# contrl.net
KiCad netlist of a schematic drawn in Altium Designer
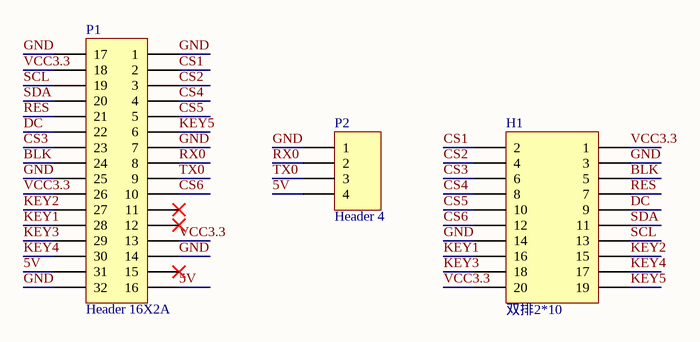
[diagram p0: contrl.SchDoc]

(export (version "E")
  (design (tool "Eeschema 10.0.6"))
  (components
    (comp (ref "H1") (value "双排2*10") (footprint "20pin") (libsource (lib "displayLCD") (part "双排2*10")))
    (comp (ref "P1")
      (value "Header 16X2A")
      (footprint "合宙esp32-c3开发板底座")
      (description "Header, 16-Pin, Dual row")
      (fields (field (name "PUBLISHER") "Altium Limited"))
      (libsource (lib "Miscellaneous Connectors") (part "Header 16X2A"))
    )
    (comp (ref "P2")
      (value "Header 4")
      (footprint "HDR1X4")
      (description "Header, 4-Pin")
      (fields (field (name "PUBLISHER") "Altium Limited"))
      (libsource (lib "Miscellaneous Connectors") (part "Header 4"))
    )
  )
  (nets
    (net (code "1") (name "/5V") (class "Default")
      (node (ref "P1") (pin "16") (pinfunction "16_16") (pintype "passive"))
      (node (ref "P1") (pin "31") (pinfunction "31_31") (pintype "passive"))
      (node (ref "P2") (pin "4") (pinfunction "4_4") (pintype "passive"))
    )
    (net (code "2") (name "/BLK") (class "Default")
      (node (ref "H1") (pin "5") (pinfunction "5_5") (pintype "passive"))
      (node (ref "P1") (pin "24") (pinfunction "24_24") (pintype "passive"))
    )
    (net (code "3") (name "/CS1") (class "Default")
      (node (ref "H1") (pin "2") (pinfunction "2_2") (pintype "passive"))
      (node (ref "P1") (pin "2") (pinfunction "2_2") (pintype "passive"))
    )
    (net (code "4") (name "/CS2") (class "Default")
      (node (ref "H1") (pin "4") (pinfunction "4_4") (pintype "passive"))
      (node (ref "P1") (pin "3") (pinfunction "3_3") (pintype "passive"))
    )
    (net (code "5") (name "/CS3") (class "Default")
      (node (ref "H1") (pin "6") (pinfunction "6_6") (pintype "passive"))
      (node (ref "P1") (pin "23") (pinfunction "23_23") (pintype "passive"))
    )
    (net (code "6") (name "/CS4") (class "Default")
      (node (ref "H1") (pin "8") (pinfunction "8_8") (pintype "passive"))
      (node (ref "P1") (pin "4") (pinfunction "4_4") (pintype "passive"))
    )
    (net (code "7") (name "/CS5") (class "Default")
      (node (ref "H1") (pin "10") (pinfunction "10_10") (pintype "passive"))
      (node (ref "P1") (pin "5") (pinfunction "5_5") (pintype "passive"))
    )
    (net (code "8") (name "/CS6") (class "Default")
      (node (ref "H1") (pin "12") (pinfunction "12_12") (pintype "passive"))
      (node (ref "P1") (pin "10") (pinfunction "10_10") (pintype "passive"))
    )
    (net (code "9") (name "/DC") (class "Default")
      (node (ref "H1") (pin "9") (pinfunction "9_9") (pintype "passive"))
      (node (ref "P1") (pin "22") (pinfunction "22_22") (pintype "passive"))
    )
    (net (code "10") (name "/GND") (class "Default")
      (node (ref "H1") (pin "14") (pinfunction "14_14") (pintype "passive"))
      (node (ref "H1") (pin "3") (pinfunction "3_3") (pintype "passive"))
      (node (ref "P1") (pin "1") (pinfunction "1_1") (pintype "passive"))
      (node (ref "P1") (pin "14") (pinfunction "14_14") (pintype "passive"))
      (node (ref "P1") (pin "17") (pinfunction "17_17") (pintype "passive"))
      (node (ref "P1") (pin "25") (pinfunction "25_25") (pintype "passive"))
      (node (ref "P1") (pin "32") (pinfunction "32_32") (pintype "passive"))
      (node (ref "P1") (pin "7") (pinfunction "7_7") (pintype "passive"))
      (node (ref "P2") (pin "1") (pinfunction "1_1") (pintype "passive"))
    )
    (net (code "11") (name "/KEY1") (class "Default")
      (node (ref "H1") (pin "16") (pinfunction "16_16") (pintype "passive"))
      (node (ref "P1") (pin "28") (pinfunction "28_28") (pintype "passive"))
    )
    (net (code "12") (name "/KEY2") (class "Default")
      (node (ref "H1") (pin "15") (pinfunction "15_15") (pintype "passive"))
      (node (ref "P1") (pin "27") (pinfunction "27_27") (pintype "passive"))
    )
    (net (code "13") (name "/KEY3") (class "Default")
      (node (ref "H1") (pin "18") (pinfunction "18_18") (pintype "passive"))
      (node (ref "P1") (pin "29") (pinfunction "29_29") (pintype "passive"))
    )
    (net (code "14") (name "/KEY4") (class "Default")
      (node (ref "H1") (pin "17") (pinfunction "17_17") (pintype "passive"))
      (node (ref "P1") (pin "30") (pinfunction "30_30") (pintype "passive"))
    )
    (net (code "15") (name "/KEY5") (class "Default")
      (node (ref "H1") (pin "19") (pinfunction "19_19") (pintype "passive"))
      (node (ref "P1") (pin "6") (pinfunction "6_6") (pintype "passive"))
    )
    (net (code "16") (name "/RES") (class "Default")
      (node (ref "H1") (pin "7") (pinfunction "7_7") (pintype "passive"))
      (node (ref "P1") (pin "21") (pinfunction "21_21") (pintype "passive"))
    )
    (net (code "17") (name "/RX0") (class "Default")
      (node (ref "P1") (pin "8") (pinfunction "8_8") (pintype "passive"))
      (node (ref "P2") (pin "2") (pinfunction "2_2") (pintype "passive"))
    )
    (net (code "18") (name "/SCL") (class "Default")
      (node (ref "H1") (pin "13") (pinfunction "13_13") (pintype "passive"))
      (node (ref "P1") (pin "19") (pinfunction "19_19") (pintype "passive"))
    )
    (net (code "19") (name "/SDA") (class "Default")
      (node (ref "H1") (pin "11") (pinfunction "11_11") (pintype "passive"))
      (node (ref "P1") (pin "20") (pinfunction "20_20") (pintype "passive"))
    )
    (net (code "20") (name "/TX0") (class "Default")
      (node (ref "P1") (pin "9") (pinfunction "9_9") (pintype "passive"))
      (node (ref "P2") (pin "3") (pinfunction "3_3") (pintype "passive"))
    )
    (net (code "21") (name "/VCC3.3") (class "Default")
      (node (ref "H1") (pin "1") (pinfunction "1_1") (pintype "passive"))
      (node (ref "H1") (pin "20") (pinfunction "20_20") (pintype "passive"))
      (node (ref "P1") (pin "13") (pinfunction "13_13") (pintype "passive"))
      (node (ref "P1") (pin "18") (pinfunction "18_18") (pintype "passive"))
      (node (ref "P1") (pin "26") (pinfunction "26_26") (pintype "passive"))
    )
    (net (code "22") (name "unconnected-(P1-Pad11)") (class "Default")
      (node (ref "P1") (pin "11") (pinfunction "11_11") (pintype "passive+no_connect"))
    )
    (net (code "23") (name "unconnected-(P1-Pad12)") (class "Default")
      (node (ref "P1") (pin "12") (pinfunction "12_12") (pintype "passive+no_connect"))
    )
    (net (code "24") (name "unconnected-(P1-Pad15)") (class "Default")
      (node (ref "P1") (pin "15") (pinfunction "15_15") (pintype "passive+no_connect"))
    )
  )
)
